# BUF802_Main.net
KiCad netlist of a schematic drawn in Altium Designer
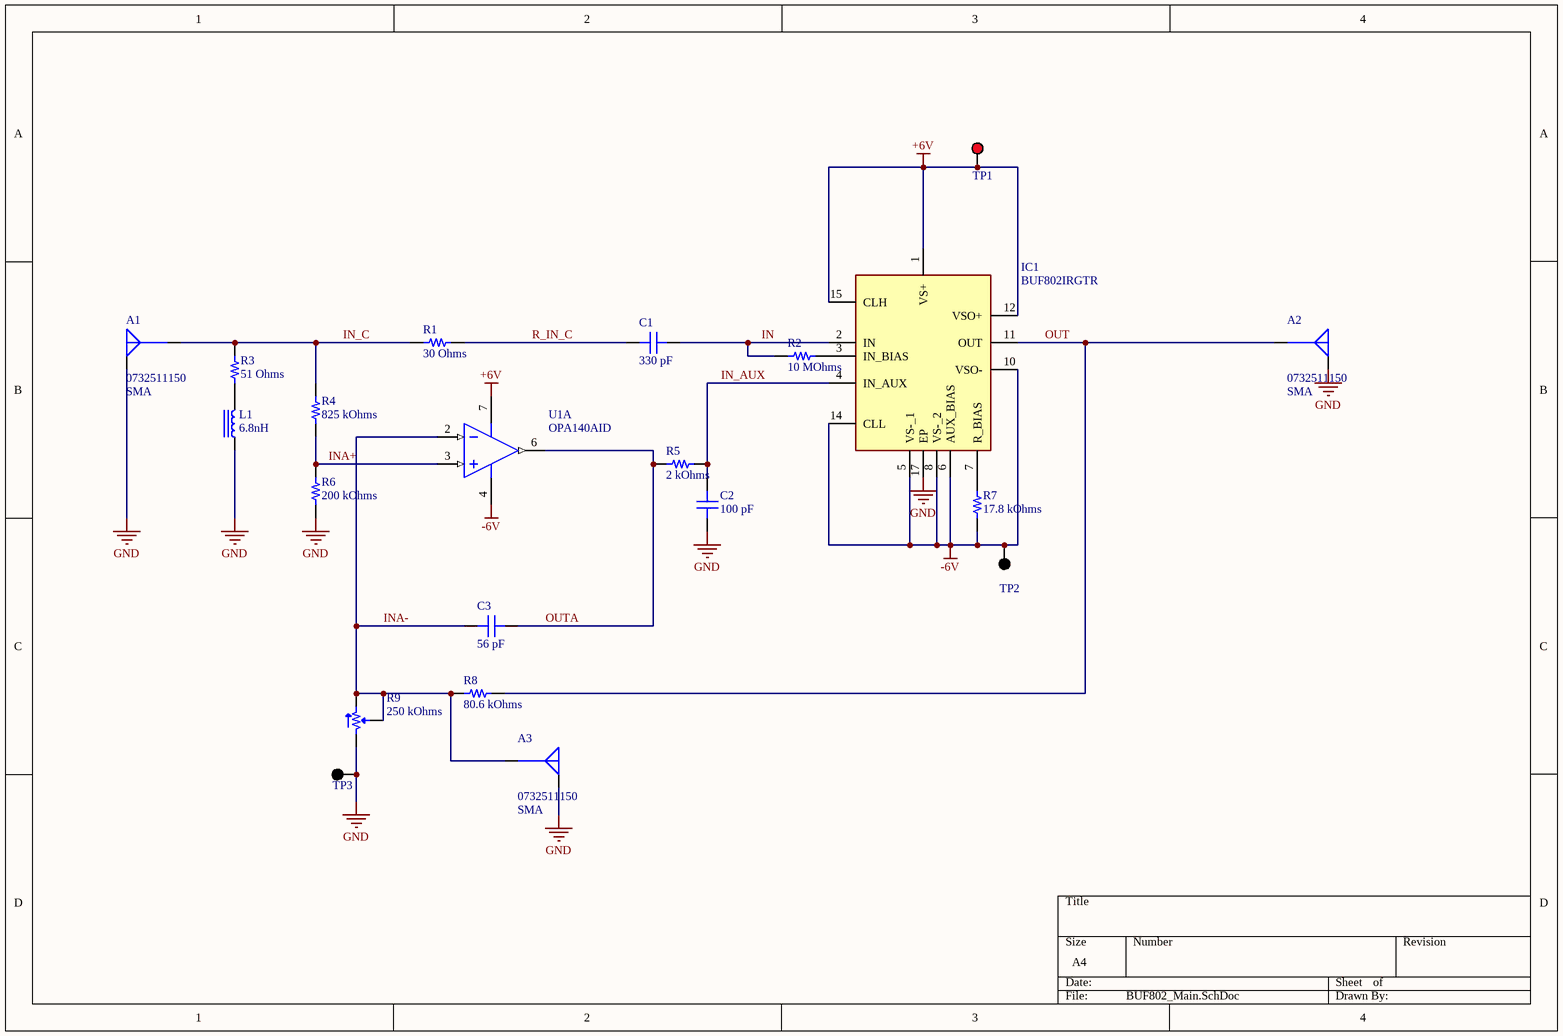
[diagram p0: BUF802_Main.SchDoc]

(export (version "E")
  (design (tool "Eeschema 10.0.6"))
  (components
    (comp (ref "A1")
      (value "0732511150")
      (footprint "MOLEX SD-73251-115")
      (description "CONN SMA RCPT STR 50OHM EDGE MNT")
      (fields (field (name "CONNECTOR STYLE") "SMA") (field (name "MANUFACTURER") "Molex"))
      (libsource (lib "Celestial Altium Library - altium_library") (part "Basic Antenna"))
    )
    (comp (ref "A2")
      (value "0732511150")
      (footprint "MOLEX SD-73251-115")
      (description "CONN SMA RCPT STR 50OHM EDGE MNT")
      (fields (field (name "CONNECTOR STYLE") "SMA") (field (name "MANUFACTURER") "Molex"))
      (libsource (lib "Celestial Altium Library - altium_library") (part "Basic Antenna"))
    )
    (comp (ref "A3")
      (value "0732511150")
      (footprint "MOLEX SD-73251-115")
      (description "CONN SMA RCPT STR 50OHM EDGE MNT")
      (fields (field (name "CONNECTOR STYLE") "SMA") (field (name "MANUFACTURER") "Molex"))
      (libsource (lib "Celestial Altium Library - altium_library") (part "Basic Antenna"))
    )
    (comp (ref "C1")
      (value "330 pF")
      (footprint "CAP 0805_2012")
      (description "CAP CER 330PF 500V C0G/NP0 0805")
      (fields (field (name "PART NUMBER") "0805N331K501NT") (field (name "MANUFACTURER") "Knowles Novacap"))
      (libsource (lib "Celestial Altium Library - altium_library") (part "Capacitor"))
    )
    (comp (ref "C2")
      (value "100 pF")
      (footprint "CAP 0805_2012")
      (description "CAP CER 100PF 500V C0G/NP0 0805")
      (fields
        (field (name "PART NUMBER") "501R15N101KV4T")
        (field (name "MANUFACTURER") "Johanson Dielectrics Inc.")
      )
      (libsource (lib "Celestial Altium Library - altium_library") (part "Capacitor"))
    )
    (comp (ref "C3")
      (value "56 pF")
      (footprint "CAP 0805_2012")
      (description "CAP CER 56PF 250V NP0 0805")
      (fields
        (field (name "PART NUMBER") "251R15S560GV4E")
        (field (name "MANUFACTURER") "Johanson Technology Inc.")
      )
      (libsource (lib "Celestial Altium Library - altium_library") (part "Capacitor"))
    )
    (comp (ref "IC1")
      (value "BUF802IRGTR")
      (footprint "QFN50P300X300X100-17N-D")
      (description "Integrated Circuit")
      (fields (field (name "MOUSER PART NUMBER") "595-BUF802IRGTR"))
      (libsource (lib "SamacSys") (part "BUF802IRGTR"))
    )
    (comp (ref "L1")
      (value "6.8nH")
      (footprint "IND 0603_1608 RF WW")
      (description "FIXED IND 6.8NH 1.4A 42 MOHM SMD")
      (fields (field (name "PART NUMBER") "744917068") (field (name "MANUFACTURER") "Würth Elektronik"))
      (libsource (lib "Celestial Altium Library - altium_library") (part "Inductor"))
    )
    (comp (ref "R1")
      (value "30 Ohms")
      (footprint "RES 0805_2012")
      (description "RES SMD 30 OHM 1% 1/8W 0805")
      (fields (field (name "PART NUMBER") "AC0805FR-0730RL") (field (name "MANUFACTURER") "Yageo"))
      (libsource (lib "Celestial Altium Library - altium_library") (part "Resistor"))
    )
    (comp (ref "R2")
      (value "10 MOhms")
      (footprint "RES 0805_2012")
      (description "RES SMD 10M OHM 5% 1/8W 0805")
      (fields
        (field (name "PART NUMBER") "ERJ-6GEYJ106V")
        (field (name "MANUFACTURER") "Panasonic Electronic Components")
      )
      (libsource (lib "Celestial Altium Library - altium_library") (part "Resistor"))
    )
    (comp (ref "R3")
      (value "51 Ohms")
      (footprint "RES 0805_2012")
      (description "RES SMD 51 OHM 1% 1/8W 0805")
      (fields (field (name "PART NUMBER") "CR0805-FX-51R0ELF") (field (name "MANUFACTURER") "Bourns Inc."))
      (libsource (lib "Celestial Altium Library - altium_library") (part "Resistor"))
    )
    (comp (ref "R4")
      (value "825 kOhms")
      (footprint "RES 0805_2012")
      (description "RES 825K OHM 0.1% 1/8W 0805")
      (fields
        (field (name "PART NUMBER") "ERA-6AEB8253V")
        (field (name "MANUFACTURER") "Panasonic Electronic Components")
      )
      (libsource (lib "Celestial Altium Library - altium_library") (part "Resistor"))
    )
    (comp (ref "R5")
      (value "2 kOhms")
      (footprint "RES 0805_2012")
      (description "RES 2K OHM 0.1% 1/8W 0805")
      (fields
        (field (name "PART NUMBER") "ERA-6AEB202V")
        (field (name "MANUFACTURER") "Panasonic Electronic Components")
      )
      (libsource (lib "Celestial Altium Library - altium_library") (part "Resistor"))
    )
    (comp (ref "R6")
      (value "200 kOhms")
      (footprint "RES 0805_2012")
      (description "RES 200K OHM 0.1% 1/8W 0805")
      (fields
        (field (name "PART NUMBER") "ERA-6AEB204V")
        (field (name "MANUFACTURER") "Panasonic Electronic Components")
      )
      (libsource (lib "Celestial Altium Library - altium_library") (part "Resistor"))
    )
    (comp (ref "R7")
      (value "17.8 kOhms")
      (footprint "RES 0805_2012")
      (description "RES SMD 17.8K OHM 0.1% 1/4W 0805")
      (fields
        (field (name "PART NUMBER") "ERJ-PB6B1782V")
        (field (name "MANUFACTURER") "Panasonic Electronic Components")
      )
      (libsource (lib "Celestial Altium Library - altium_library") (part "Resistor"))
    )
    (comp (ref "R8")
      (value "80.6 kOhms")
      (footprint "RES 0805_2012")
      (description "RES 80.6K OHM 0.1% 1/8W 0805")
      (fields
        (field (name "PART NUMBER") "ERA-6AEB8062V")
        (field (name "MANUFACTURER") "Panasonic Electronic Components")
      )
      (libsource (lib "Celestial Altium Library - altium_library") (part "Resistor"))
    )
    (comp (ref "R9")
      (value "250 kOhms")
      (footprint "BOURNS TRIMPOT 3296W")
      (description "TRIMMER 250K OHM 0.5W PC PIN TOP")
      (fields (field (name "PART NUMBER") "3296W-1-254LF") (field (name "MANUFACTURER") "Bourns Inc."))
      (libsource (lib "Celestial Altium Library - altium_library") (part "Potentiometer"))
    )
    (comp (ref "TP1")
      (value "5000")
      (footprint "Keystone5000")
      (description "Test Point, Miniature, Red, TH")
      (fields (field (name "MANUFACTURER") "Keystone") (field (name "PUBLISHER") "Texas Instruments"))
      (libsource (lib "TIDA-01022-E2") (part "5000"))
    )
    (comp (ref "TP2")
      (value "5001")
      (footprint "Keystone5001")
      (description "Test Point, Miniature, Black, TH")
      (fields (field (name "MANUFACTURER") "Keystone") (field (name "PUBLISHER") "Texas Instruments"))
      (libsource (lib "TIDA-01022-E2") (part "5001"))
    )
    (comp (ref "TP3")
      (value "5001")
      (footprint "Keystone5001")
      (description "Test Point, Miniature, Black, TH")
      (fields (field (name "MANUFACTURER") "Keystone") (field (name "PUBLISHER") "Texas Instruments"))
      (libsource (lib "TIDA-01022-E2") (part "5001"))
    )
    (comp (ref "U1")
      (value "OPA140AID")
      (footprint "D0008A_M")
      (fields (field (name "MANUFACTURER") "Texas Instruments"))
      (libsource (lib "Altium Content Vault") (part "TI-OPA-8_1"))
    )
  )
  (nets
    (net (code "1") (name "+6V") (class "Default")
      (node (ref "IC1") (pin "1") (pinfunction "VS+_1") (pintype "passive"))
      (node (ref "IC1") (pin "12") (pinfunction "VSO+_12") (pintype "passive"))
      (node (ref "IC1") (pin "15") (pinfunction "CLH_15") (pintype "passive"))
      (node (ref "TP1") (pin "1") (pintype "passive"))
      (node (ref "U1") (pin "7") (pinfunction "V+_7") (pintype "power_in"))
    )
    (net (code "2") (name "-6V") (class "Default")
      (node (ref "IC1") (pin "10") (pinfunction "VSO-_10") (pintype "passive"))
      (node (ref "IC1") (pin "14") (pinfunction "CLL_14") (pintype "passive"))
      (node (ref "IC1") (pin "5") (pinfunction "VS-_1_5") (pintype "passive"))
      (node (ref "IC1") (pin "6") (pinfunction "AUX_BIAS_6") (pintype "passive"))
      (node (ref "IC1") (pin "8") (pinfunction "VS-_2_8") (pintype "passive"))
      (node (ref "R7") (pin "1") (pinfunction "1_1") (pintype "passive"))
      (node (ref "TP2") (pin "1") (pintype "passive"))
      (node (ref "U1") (pin "4") (pinfunction "V-_4") (pintype "power_in"))
    )
    (net (code "3") (name "/IN") (class "Default")
      (node (ref "C1") (pin "2") (pinfunction "2_2") (pintype "passive"))
      (node (ref "IC1") (pin "2") (pinfunction "IN_2") (pintype "passive"))
      (node (ref "R2") (pin "1") (pinfunction "1_1") (pintype "passive"))
    )
    (net (code "4") (name "/INA+") (class "Default")
      (node (ref "R4") (pin "1") (pinfunction "1_1") (pintype "passive"))
      (node (ref "R6") (pin "2") (pinfunction "2_2") (pintype "passive"))
      (node (ref "U1") (pin "3") (pinfunction "IN+_3") (pintype "input"))
    )
    (net (code "5") (name "/INA-") (class "Default")
      (node (ref "A3") (pin "S") (pinfunction "S_S") (pintype "passive"))
      (node (ref "C3") (pin "1") (pinfunction "1_1") (pintype "passive"))
      (node (ref "R8") (pin "1") (pinfunction "1_1") (pintype "passive"))
      (node (ref "R9") (pin "2") (pinfunction "2_2") (pintype "passive"))
      (node (ref "R9") (pin "3") (pinfunction "3_3") (pintype "passive"))
      (node (ref "U1") (pin "2") (pinfunction "IN-_2") (pintype "input"))
    )
    (net (code "6") (name "/IN_AUX") (class "Default")
      (node (ref "C2") (pin "2") (pinfunction "2_2") (pintype "passive"))
      (node (ref "IC1") (pin "4") (pinfunction "IN_AUX_4") (pintype "passive"))
      (node (ref "R5") (pin "2") (pinfunction "2_2") (pintype "passive"))
    )
    (net (code "7") (name "/IN_C") (class "Default")
      (node (ref "A1") (pin "S") (pinfunction "S_S") (pintype "passive"))
      (node (ref "R1") (pin "1") (pinfunction "1_1") (pintype "passive"))
      (node (ref "R3") (pin "2") (pinfunction "2_2") (pintype "passive"))
      (node (ref "R4") (pin "2") (pinfunction "2_2") (pintype "passive"))
    )
    (net (code "8") (name "/OUT") (class "Default")
      (node (ref "A2") (pin "S") (pinfunction "S_S") (pintype "passive"))
      (node (ref "IC1") (pin "11") (pinfunction "OUT_11") (pintype "passive"))
      (node (ref "R8") (pin "2") (pinfunction "2_2") (pintype "passive"))
    )
    (net (code "9") (name "/OUTA") (class "Default")
      (node (ref "C3") (pin "2") (pinfunction "2_2") (pintype "passive"))
      (node (ref "R5") (pin "1") (pinfunction "1_1") (pintype "passive"))
      (node (ref "U1") (pin "6") (pinfunction "OUT_6") (pintype "output"))
    )
    (net (code "10") (name "/R_IN_C") (class "Default")
      (node (ref "C1") (pin "1") (pinfunction "1_1") (pintype "passive"))
      (node (ref "R1") (pin "2") (pinfunction "2_2") (pintype "passive"))
    )
    (net (code "11") (name "GND") (class "Default")
      (node (ref "A1") (pin "G") (pinfunction "G_G") (pintype "passive"))
      (node (ref "A2") (pin "G") (pinfunction "G_G") (pintype "passive"))
      (node (ref "A3") (pin "G") (pinfunction "G_G") (pintype "passive"))
      (node (ref "C2") (pin "1") (pinfunction "1_1") (pintype "passive"))
      (node (ref "IC1") (pin "17") (pinfunction "EP_17") (pintype "passive"))
      (node (ref "L1") (pin "1") (pinfunction "1_1") (pintype "passive"))
      (node (ref "R6") (pin "1") (pinfunction "1_1") (pintype "passive"))
      (node (ref "R9") (pin "1") (pinfunction "1_1") (pintype "passive"))
      (node (ref "TP3") (pin "1") (pintype "passive"))
    )
    (net (code "12") (name "Net-(IC1-IN_BIAS)") (class "Default")
      (node (ref "IC1") (pin "3") (pinfunction "IN_BIAS_3") (pintype "passive"))
      (node (ref "R2") (pin "2") (pinfunction "2_2") (pintype "passive"))
    )
    (net (code "13") (name "Net-(IC1-R_BIAS)") (class "Default")
      (node (ref "IC1") (pin "7") (pinfunction "R_BIAS_7") (pintype "passive"))
      (node (ref "R7") (pin "2") (pinfunction "2_2") (pintype "passive"))
    )
    (net (code "14") (name "Net-(L1-Pad2)") (class "Default")
      (node (ref "L1") (pin "2") (pinfunction "2_2") (pintype "passive"))
      (node (ref "R3") (pin "1") (pinfunction "1_1") (pintype "passive"))
    )
  )
)
